# flexibleConnector.net
KiCad netlist of a schematic drawn in EAGLE
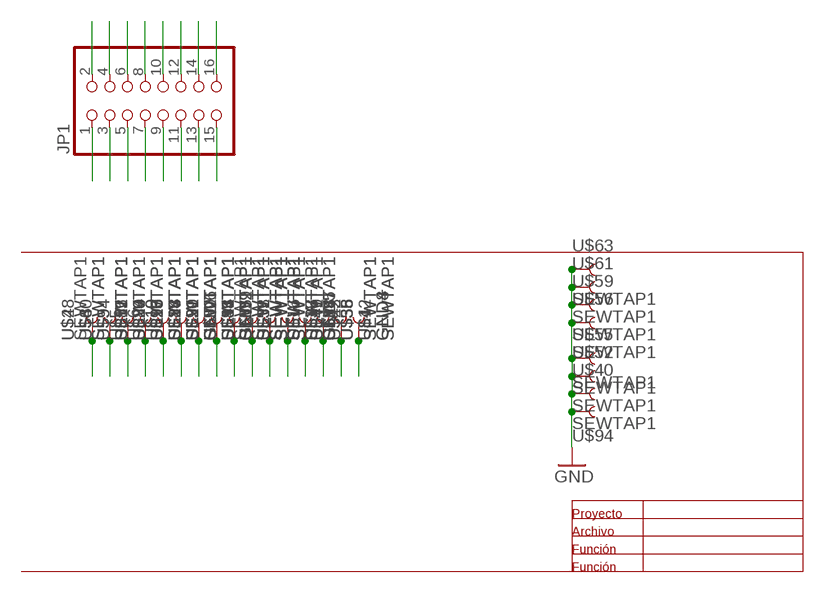
[diagram p0: schematic, sheet 1]

(export (version "E")
  (design (tool "Eeschema 10.0.6"))
  (components
    (comp (ref "GND1")
      (value "SEWTAP1")
      (footprint "eagle-import:PETAL-LONG-1")
      (libsource (lib "eagle-import") (part "SEWTAP1"))
    )
    (comp (ref "GND2")
      (value "SEWTAP1")
      (footprint "eagle-import:PETAL-LONG-1")
      (libsource (lib "eagle-import") (part "SEWTAP1"))
    )
    (comp (ref "GND4")
      (value "SEWTAP1")
      (footprint "eagle-import:PETAL-LONG-1")
      (libsource (lib "eagle-import") (part "SEWTAP1"))
    )
    (comp (ref "GND5")
      (value "SEWTAP1")
      (footprint "eagle-import:PETAL-LONG-1")
      (libsource (lib "eagle-import") (part "SEWTAP1"))
    )
    (comp (ref "GND6")
      (value "SEWTAP1")
      (footprint "eagle-import:PETAL-LONG-1")
      (libsource (lib "eagle-import") (part "SEWTAP1"))
    )
    (comp (ref "GND7")
      (value "SEWTAP1")
      (footprint "eagle-import:PETAL-LONG-1")
      (libsource (lib "eagle-import") (part "SEWTAP1"))
    )
    (comp (ref "GND8")
      (value "SEWTAP1")
      (footprint "eagle-import:PETAL-LONG-1")
      (libsource (lib "eagle-import") (part "SEWTAP1"))
    )
    (comp (ref "GND9")
      (value "SEWTAP1")
      (footprint "eagle-import:PETAL-LONG-1")
      (libsource (lib "eagle-import") (part "SEWTAP1"))
    )
    (comp (ref "JP1")
      (value "PINHD-2X8")
      (footprint "eagle-import:2X08")
      (libsource (lib "eagle-import") (part "PINHD-2X8"))
    )
    (comp (ref "U$1")
      (value "SEWTAP1")
      (footprint "eagle-import:PETAL-LONG-1")
      (libsource (lib "eagle-import") (part "SEWTAP1"))
    )
    (comp (ref "U$2")
      (value "SEWTAP1")
      (footprint "eagle-import:PETAL-LONG-1")
      (libsource (lib "eagle-import") (part "SEWTAP1"))
    )
    (comp (ref "U$3")
      (value "SEWTAP1")
      (footprint "eagle-import:PETAL-LONG-1")
      (libsource (lib "eagle-import") (part "SEWTAP1"))
    )
    (comp (ref "U$4")
      (value "SEWTAP1")
      (footprint "eagle-import:PETAL-LONG-1")
      (libsource (lib "eagle-import") (part "SEWTAP1"))
    )
    (comp (ref "U$5")
      (value "SEWTAP1")
      (footprint "eagle-import:PETAL-LONG-1")
      (libsource (lib "eagle-import") (part "SEWTAP1"))
    )
    (comp (ref "U$6")
      (value "SEWTAP1")
      (footprint "eagle-import:PETAL-LONG-1")
      (libsource (lib "eagle-import") (part "SEWTAP1"))
    )
    (comp (ref "U$7")
      (value "SEWTAP1")
      (footprint "eagle-import:PETAL-LONG-1")
      (libsource (lib "eagle-import") (part "SEWTAP1"))
    )
    (comp (ref "U$8")
      (value "SEWTAP1")
      (footprint "eagle-import:PETAL-LONG-1")
      (libsource (lib "eagle-import") (part "SEWTAP1"))
    )
    (comp (ref "U$9")
      (value "SEWTAP1")
      (footprint "eagle-import:PETAL-LONG-1")
      (libsource (lib "eagle-import") (part "SEWTAP1"))
    )
    (comp (ref "U$10")
      (value "SEWTAP1")
      (footprint "eagle-import:PETAL-LONG-1")
      (libsource (lib "eagle-import") (part "SEWTAP1"))
    )
    (comp (ref "U$11")
      (value "SEWTAP1")
      (footprint "eagle-import:PETAL-LONG-1")
      (libsource (lib "eagle-import") (part "SEWTAP1"))
    )
    (comp (ref "U$12")
      (value "SEWTAP1")
      (footprint "eagle-import:PETAL-LONG-1")
      (libsource (lib "eagle-import") (part "SEWTAP1"))
    )
    (comp (ref "U$13")
      (value "SEWTAP1")
      (footprint "eagle-import:PETAL-LONG-1")
      (libsource (lib "eagle-import") (part "SEWTAP1"))
    )
    (comp (ref "U$14")
      (value "SEWTAP1")
      (footprint "eagle-import:PETAL-LONG-1")
      (libsource (lib "eagle-import") (part "SEWTAP1"))
    )
    (comp (ref "U$15")
      (value "SEWTAP1")
      (footprint "eagle-import:PETAL-LONG-1")
      (libsource (lib "eagle-import") (part "SEWTAP1"))
    )
    (comp (ref "U$16")
      (value "SEWTAP1")
      (footprint "eagle-import:PETAL-LONG-1")
      (libsource (lib "eagle-import") (part "SEWTAP1"))
    )
    (comp (ref "U$17")
      (value "SEWTAP1")
      (footprint "eagle-import:PETAL-LONG-1")
      (libsource (lib "eagle-import") (part "SEWTAP1"))
    )
    (comp (ref "U$18")
      (value "SEWTAP1")
      (footprint "eagle-import:PETAL-LONG-1")
      (libsource (lib "eagle-import") (part "SEWTAP1"))
    )
    (comp (ref "U$19")
      (value "SEWTAP1")
      (footprint "eagle-import:PETAL-LONG-1")
      (libsource (lib "eagle-import") (part "SEWTAP1"))
    )
    (comp (ref "U$20")
      (value "SEWTAP1")
      (footprint "eagle-import:PETAL-LONG-1")
      (libsource (lib "eagle-import") (part "SEWTAP1"))
    )
    (comp (ref "U$21")
      (value "SEWTAP1")
      (footprint "eagle-import:PETAL-LONG-1")
      (libsource (lib "eagle-import") (part "SEWTAP1"))
    )
    (comp (ref "U$22")
      (value "SEWTAP1")
      (footprint "eagle-import:PETAL-LONG-1")
      (libsource (lib "eagle-import") (part "SEWTAP1"))
    )
    (comp (ref "U$23")
      (value "SEWTAP1")
      (footprint "eagle-import:PETAL-LONG-1")
      (libsource (lib "eagle-import") (part "SEWTAP1"))
    )
    (comp (ref "U$24")
      (value "SEWTAP1")
      (footprint "eagle-import:PETAL-LONG-1")
      (libsource (lib "eagle-import") (part "SEWTAP1"))
    )
    (comp (ref "U$25")
      (value "SEWTAP1")
      (footprint "eagle-import:PETAL-LONG-1")
      (libsource (lib "eagle-import") (part "SEWTAP1"))
    )
    (comp (ref "U$26")
      (value "SEWTAP1")
      (footprint "eagle-import:PETAL-LONG-1")
      (libsource (lib "eagle-import") (part "SEWTAP1"))
    )
    (comp (ref "U$27")
      (value "SEWTAP1")
      (footprint "eagle-import:PETAL-LONG-1")
      (libsource (lib "eagle-import") (part "SEWTAP1"))
    )
    (comp (ref "U$28")
      (value "SEWTAP1")
      (footprint "eagle-import:PETAL-LONG-1")
      (libsource (lib "eagle-import") (part "SEWTAP1"))
    )
    (comp (ref "U$29")
      (value "SEWTAP1")
      (footprint "eagle-import:PETAL-LONG-1")
      (libsource (lib "eagle-import") (part "SEWTAP1"))
    )
    (comp (ref "U$30")
      (value "SEWTAP1")
      (footprint "eagle-import:PETAL-LONG-1")
      (libsource (lib "eagle-import") (part "SEWTAP1"))
    )
    (comp (ref "U$31")
      (value "SEWTAP1")
      (footprint "eagle-import:PETAL-LONG-1")
      (libsource (lib "eagle-import") (part "SEWTAP1"))
    )
    (comp (ref "U$32")
      (value "SEWTAP1")
      (footprint "eagle-import:PETAL-LONG-1")
      (libsource (lib "eagle-import") (part "SEWTAP1"))
    )
    (comp (ref "U$33")
      (value "SEWTAP1")
      (footprint "eagle-import:PETAL-LONG-1")
      (libsource (lib "eagle-import") (part "SEWTAP1"))
    )
    (comp (ref "U$34")
      (value "SEWTAP1")
      (footprint "eagle-import:PETAL-LONG-1")
      (libsource (lib "eagle-import") (part "SEWTAP1"))
    )
    (comp (ref "U$35")
      (value "SEWTAP1")
      (footprint "eagle-import:PETAL-LONG-1")
      (libsource (lib "eagle-import") (part "SEWTAP1"))
    )
    (comp (ref "U$36")
      (value "SEWTAP1")
      (footprint "eagle-import:PETAL-LONG-1")
      (libsource (lib "eagle-import") (part "SEWTAP1"))
    )
    (comp (ref "U$38")
      (value "SEWTAP1")
      (footprint "eagle-import:PETAL-LONG-1")
      (libsource (lib "eagle-import") (part "SEWTAP1"))
    )
    (comp (ref "U$40")
      (value "SEWTAP1")
      (footprint "eagle-import:PETAL-LONG-1")
      (libsource (lib "eagle-import") (part "SEWTAP1"))
    )
    (comp (ref "U$41")
      (value "SEWTAP1")
      (footprint "eagle-import:PETAL-LONG-1")
      (libsource (lib "eagle-import") (part "SEWTAP1"))
    )
    (comp (ref "U$42")
      (value "SEWTAP1")
      (footprint "eagle-import:PETAL-LONG-1")
      (libsource (lib "eagle-import") (part "SEWTAP1"))
    )
    (comp (ref "U$43")
      (value "SEWTAP1")
      (footprint "eagle-import:PETAL-LONG-1")
      (libsource (lib "eagle-import") (part "SEWTAP1"))
    )
    (comp (ref "U$44")
      (value "SEWTAP1")
      (footprint "eagle-import:PETAL-LONG-1")
      (libsource (lib "eagle-import") (part "SEWTAP1"))
    )
    (comp (ref "U$48")
      (value "SEWTAP1")
      (footprint "eagle-import:PETAL-LONG-1")
      (libsource (lib "eagle-import") (part "SEWTAP1"))
    )
    (comp (ref "U$49")
      (value "SEWTAP1")
      (footprint "eagle-import:PETAL-LONG-1")
      (libsource (lib "eagle-import") (part "SEWTAP1"))
    )
    (comp (ref "U$50")
      (value "SEWTAP1")
      (footprint "eagle-import:PETAL-LONG-1")
      (libsource (lib "eagle-import") (part "SEWTAP1"))
    )
    (comp (ref "U$52")
      (value "SEWTAP1")
      (footprint "eagle-import:PETAL-LONG-1")
      (libsource (lib "eagle-import") (part "SEWTAP1"))
    )
    (comp (ref "U$53")
      (value "SEWTAP1")
      (footprint "eagle-import:PETAL-LONG-1")
      (libsource (lib "eagle-import") (part "SEWTAP1"))
    )
    (comp (ref "U$54")
      (value "SEWTAP1")
      (footprint "eagle-import:PETAL-LONG-1")
      (libsource (lib "eagle-import") (part "SEWTAP1"))
    )
    (comp (ref "U$55")
      (value "SEWTAP1")
      (footprint "eagle-import:PETAL-LONG-1")
      (libsource (lib "eagle-import") (part "SEWTAP1"))
    )
    (comp (ref "U$56")
      (value "SEWTAP1")
      (footprint "eagle-import:PETAL-LONG-1")
      (libsource (lib "eagle-import") (part "SEWTAP1"))
    )
    (comp (ref "U$58")
      (value "SEWTAP1")
      (footprint "eagle-import:PETAL-LONG-1")
      (libsource (lib "eagle-import") (part "SEWTAP1"))
    )
    (comp (ref "U$59")
      (value "SEWTAP1")
      (footprint "eagle-import:PETAL-LONG-1")
      (libsource (lib "eagle-import") (part "SEWTAP1"))
    )
    (comp (ref "U$60")
      (value "SEWTAP1")
      (footprint "eagle-import:PETAL-LONG-1")
      (libsource (lib "eagle-import") (part "SEWTAP1"))
    )
    (comp (ref "U$61")
      (value "SEWTAP1")
      (footprint "eagle-import:PETAL-LONG-1")
      (libsource (lib "eagle-import") (part "SEWTAP1"))
    )
    (comp (ref "U$63")
      (value "SEWTAP1")
      (footprint "eagle-import:PETAL-LONG-1")
      (libsource (lib "eagle-import") (part "SEWTAP1"))
    )
    (comp (ref "U$65")
      (value "SEWTAP1")
      (footprint "eagle-import:PETAL-LONG-1")
      (libsource (lib "eagle-import") (part "SEWTAP1"))
    )
    (comp (ref "U$85")
      (value "SEWTAP1")
      (footprint "eagle-import:PETAL-LONG-1")
      (libsource (lib "eagle-import") (part "SEWTAP1"))
    )
    (comp (ref "U$88")
      (value "SEWTAP1")
      (footprint "eagle-import:PETAL-LONG-1")
      (libsource (lib "eagle-import") (part "SEWTAP1"))
    )
    (comp (ref "U$89")
      (value "SEWTAP1")
      (footprint "eagle-import:PETAL-LONG-1")
      (libsource (lib "eagle-import") (part "SEWTAP1"))
    )
    (comp (ref "U$90")
      (value "SEWTAP1")
      (footprint "eagle-import:PETAL-LONG-1")
      (libsource (lib "eagle-import") (part "SEWTAP1"))
    )
    (comp (ref "U$91")
      (value "SEWTAP1")
      (footprint "eagle-import:PETAL-LONG-1")
      (libsource (lib "eagle-import") (part "SEWTAP1"))
    )
    (comp (ref "U$92")
      (value "SEWTAP1")
      (footprint "eagle-import:PETAL-LONG-1")
      (libsource (lib "eagle-import") (part "SEWTAP1"))
    )
    (comp (ref "U$93")
      (value "SEWTAP1")
      (footprint "eagle-import:PETAL-LONG-1")
      (libsource (lib "eagle-import") (part "SEWTAP1"))
    )
    (comp (ref "U$94")
      (value "SEWTAP1")
      (footprint "eagle-import:PETAL-LONG-1")
      (libsource (lib "eagle-import") (part "SEWTAP1"))
    )
  )
  (nets
    (net (code "1") (name "/1") (class "Default")
      (node (ref "GND4") (pin "1") (pinfunction "1_1") (pintype "bidirectional"))
      (node (ref "GND8") (pin "1") (pinfunction "1_1") (pintype "bidirectional"))
      (node (ref "JP1") (pin "1") (pinfunction "1_1") (pintype "passive"))
      (node (ref "U$22") (pin "1") (pinfunction "1_1") (pintype "bidirectional"))
      (node (ref "U$43") (pin "1") (pinfunction "1_1") (pintype "bidirectional"))
    )
    (net (code "2") (name "/2") (class "Default")
      (node (ref "JP1") (pin "2") (pinfunction "2_2") (pintype "passive"))
      (node (ref "U$1") (pin "1") (pinfunction "1_1") (pintype "bidirectional"))
      (node (ref "U$41") (pin "1") (pinfunction "1_1") (pintype "bidirectional"))
      (node (ref "U$42") (pin "1") (pinfunction "1_1") (pintype "bidirectional"))
      (node (ref "U$49") (pin "1") (pinfunction "1_1") (pintype "bidirectional"))
    )
    (net (code "3") (name "/3") (class "Default")
      (node (ref "JP1") (pin "3") (pinfunction "3_3") (pintype "passive"))
      (node (ref "U$35") (pin "1") (pinfunction "1_1") (pintype "bidirectional"))
      (node (ref "U$36") (pin "1") (pinfunction "1_1") (pintype "bidirectional"))
      (node (ref "U$38") (pin "1") (pinfunction "1_1") (pintype "bidirectional"))
      (node (ref "U$58") (pin "1") (pinfunction "1_1") (pintype "bidirectional"))
    )
    (net (code "4") (name "/4") (class "Default")
      (node (ref "GND5") (pin "1") (pinfunction "1_1") (pintype "bidirectional"))
      (node (ref "GND7") (pin "1") (pinfunction "1_1") (pintype "bidirectional"))
      (node (ref "JP1") (pin "4") (pinfunction "4_4") (pintype "passive"))
      (node (ref "U$18") (pin "1") (pinfunction "1_1") (pintype "bidirectional"))
      (node (ref "U$34") (pin "1") (pinfunction "1_1") (pintype "bidirectional"))
    )
    (net (code "5") (name "/5") (class "Default")
      (node (ref "JP1") (pin "5") (pinfunction "5_5") (pintype "passive"))
      (node (ref "U$17") (pin "1") (pinfunction "1_1") (pintype "bidirectional"))
      (node (ref "U$32") (pin "1") (pinfunction "1_1") (pintype "bidirectional"))
      (node (ref "U$33") (pin "1") (pinfunction "1_1") (pintype "bidirectional"))
      (node (ref "U$53") (pin "1") (pinfunction "1_1") (pintype "bidirectional"))
    )
    (net (code "6") (name "/6") (class "Default")
      (node (ref "GND2") (pin "1") (pinfunction "1_1") (pintype "bidirectional"))
      (node (ref "GND9") (pin "1") (pinfunction "1_1") (pintype "bidirectional"))
      (node (ref "JP1") (pin "6") (pinfunction "6_6") (pintype "passive"))
      (node (ref "U$16") (pin "1") (pinfunction "1_1") (pintype "bidirectional"))
      (node (ref "U$65") (pin "1") (pinfunction "1_1") (pintype "bidirectional"))
    )
    (net (code "7") (name "/7") (class "Default")
      (node (ref "JP1") (pin "7") (pinfunction "7_7") (pintype "passive"))
      (node (ref "U$15") (pin "1") (pinfunction "1_1") (pintype "bidirectional"))
      (node (ref "U$31") (pin "1") (pinfunction "1_1") (pintype "bidirectional"))
      (node (ref "U$44") (pin "1") (pinfunction "1_1") (pintype "bidirectional"))
      (node (ref "U$93") (pin "1") (pinfunction "1_1") (pintype "bidirectional"))
    )
    (net (code "8") (name "/8") (class "Default")
      (node (ref "GND1") (pin "1") (pinfunction "1_1") (pintype "bidirectional"))
      (node (ref "GND6") (pin "1") (pinfunction "1_1") (pintype "bidirectional"))
      (node (ref "JP1") (pin "8") (pinfunction "8_8") (pintype "passive"))
      (node (ref "U$50") (pin "1") (pinfunction "1_1") (pintype "bidirectional"))
      (node (ref "U$92") (pin "1") (pinfunction "1_1") (pintype "bidirectional"))
    )
    (net (code "9") (name "/9") (class "Default")
      (node (ref "JP1") (pin "9") (pinfunction "9_9") (pintype "passive"))
      (node (ref "U$21") (pin "1") (pinfunction "1_1") (pintype "bidirectional"))
      (node (ref "U$29") (pin "1") (pinfunction "1_1") (pintype "bidirectional"))
      (node (ref "U$30") (pin "1") (pinfunction "1_1") (pintype "bidirectional"))
      (node (ref "U$91") (pin "1") (pinfunction "1_1") (pintype "bidirectional"))
    )
    (net (code "10") (name "/10") (class "Default")
      (node (ref "JP1") (pin "10") (pinfunction "10_10") (pintype "passive"))
      (node (ref "U$14") (pin "1") (pinfunction "1_1") (pintype "bidirectional"))
      (node (ref "U$27") (pin "1") (pinfunction "1_1") (pintype "bidirectional"))
      (node (ref "U$28") (pin "1") (pinfunction "1_1") (pintype "bidirectional"))
      (node (ref "U$88") (pin "1") (pinfunction "1_1") (pintype "bidirectional"))
    )
    (net (code "11") (name "/11") (class "Default")
      (node (ref "JP1") (pin "11") (pinfunction "11_11") (pintype "passive"))
      (node (ref "U$13") (pin "1") (pinfunction "1_1") (pintype "bidirectional"))
      (node (ref "U$25") (pin "1") (pinfunction "1_1") (pintype "bidirectional"))
      (node (ref "U$26") (pin "1") (pinfunction "1_1") (pintype "bidirectional"))
      (node (ref "U$90") (pin "1") (pinfunction "1_1") (pintype "bidirectional"))
    )
    (net (code "12") (name "/12") (class "Default")
      (node (ref "JP1") (pin "12") (pinfunction "12_12") (pintype "passive"))
      (node (ref "U$20") (pin "1") (pinfunction "1_1") (pintype "bidirectional"))
      (node (ref "U$23") (pin "1") (pinfunction "1_1") (pintype "bidirectional"))
      (node (ref "U$24") (pin "1") (pinfunction "1_1") (pintype "bidirectional"))
      (node (ref "U$89") (pin "1") (pinfunction "1_1") (pintype "bidirectional"))
    )
    (net (code "13") (name "/13") (class "Default")
      (node (ref "JP1") (pin "13") (pinfunction "13_13") (pintype "passive"))
      (node (ref "U$11") (pin "1") (pinfunction "1_1") (pintype "bidirectional"))
      (node (ref "U$12") (pin "1") (pinfunction "1_1") (pintype "bidirectional"))
      (node (ref "U$7") (pin "1") (pinfunction "1_1") (pintype "bidirectional"))
      (node (ref "U$85") (pin "1") (pinfunction "1_1") (pintype "bidirectional"))
    )
    (net (code "14") (name "/14") (class "Default")
      (node (ref "JP1") (pin "14") (pinfunction "14_14") (pintype "passive"))
      (node (ref "U$10") (pin "1") (pinfunction "1_1") (pintype "bidirectional"))
      (node (ref "U$19") (pin "1") (pinfunction "1_1") (pintype "bidirectional"))
      (node (ref "U$54") (pin "1") (pinfunction "1_1") (pintype "bidirectional"))
      (node (ref "U$9") (pin "1") (pinfunction "1_1") (pintype "bidirectional"))
    )
    (net (code "15") (name "/15") (class "Default")
      (node (ref "JP1") (pin "15") (pinfunction "15_15") (pintype "passive"))
      (node (ref "U$4") (pin "1") (pinfunction "1_1") (pintype "bidirectional"))
      (node (ref "U$6") (pin "1") (pinfunction "1_1") (pintype "bidirectional"))
      (node (ref "U$60") (pin "1") (pinfunction "1_1") (pintype "bidirectional"))
      (node (ref "U$8") (pin "1") (pinfunction "1_1") (pintype "bidirectional"))
    )
    (net (code "16") (name "/16") (class "Default")
      (node (ref "JP1") (pin "16") (pinfunction "16_16") (pintype "passive"))
      (node (ref "U$2") (pin "1") (pinfunction "1_1") (pintype "bidirectional"))
      (node (ref "U$3") (pin "1") (pinfunction "1_1") (pintype "bidirectional"))
      (node (ref "U$48") (pin "1") (pinfunction "1_1") (pintype "bidirectional"))
      (node (ref "U$5") (pin "1") (pinfunction "1_1") (pintype "bidirectional"))
    )
    (net (code "17") (name "GND") (class "Default")
      (node (ref "U$40") (pin "1") (pinfunction "1_1") (pintype "bidirectional"))
      (node (ref "U$52") (pin "1") (pinfunction "1_1") (pintype "bidirectional"))
      (node (ref "U$55") (pin "1") (pinfunction "1_1") (pintype "bidirectional"))
      (node (ref "U$56") (pin "1") (pinfunction "1_1") (pintype "bidirectional"))
      (node (ref "U$59") (pin "1") (pinfunction "1_1") (pintype "bidirectional"))
      (node (ref "U$61") (pin "1") (pinfunction "1_1") (pintype "bidirectional"))
      (node (ref "U$63") (pin "1") (pinfunction "1_1") (pintype "bidirectional"))
      (node (ref "U$94") (pin "1") (pinfunction "1_1") (pintype "bidirectional"))
    )
  )
)
